# RTI-Dome-eth-ESP32.net
KiCad netlist of a schematic drawn in EAGLE
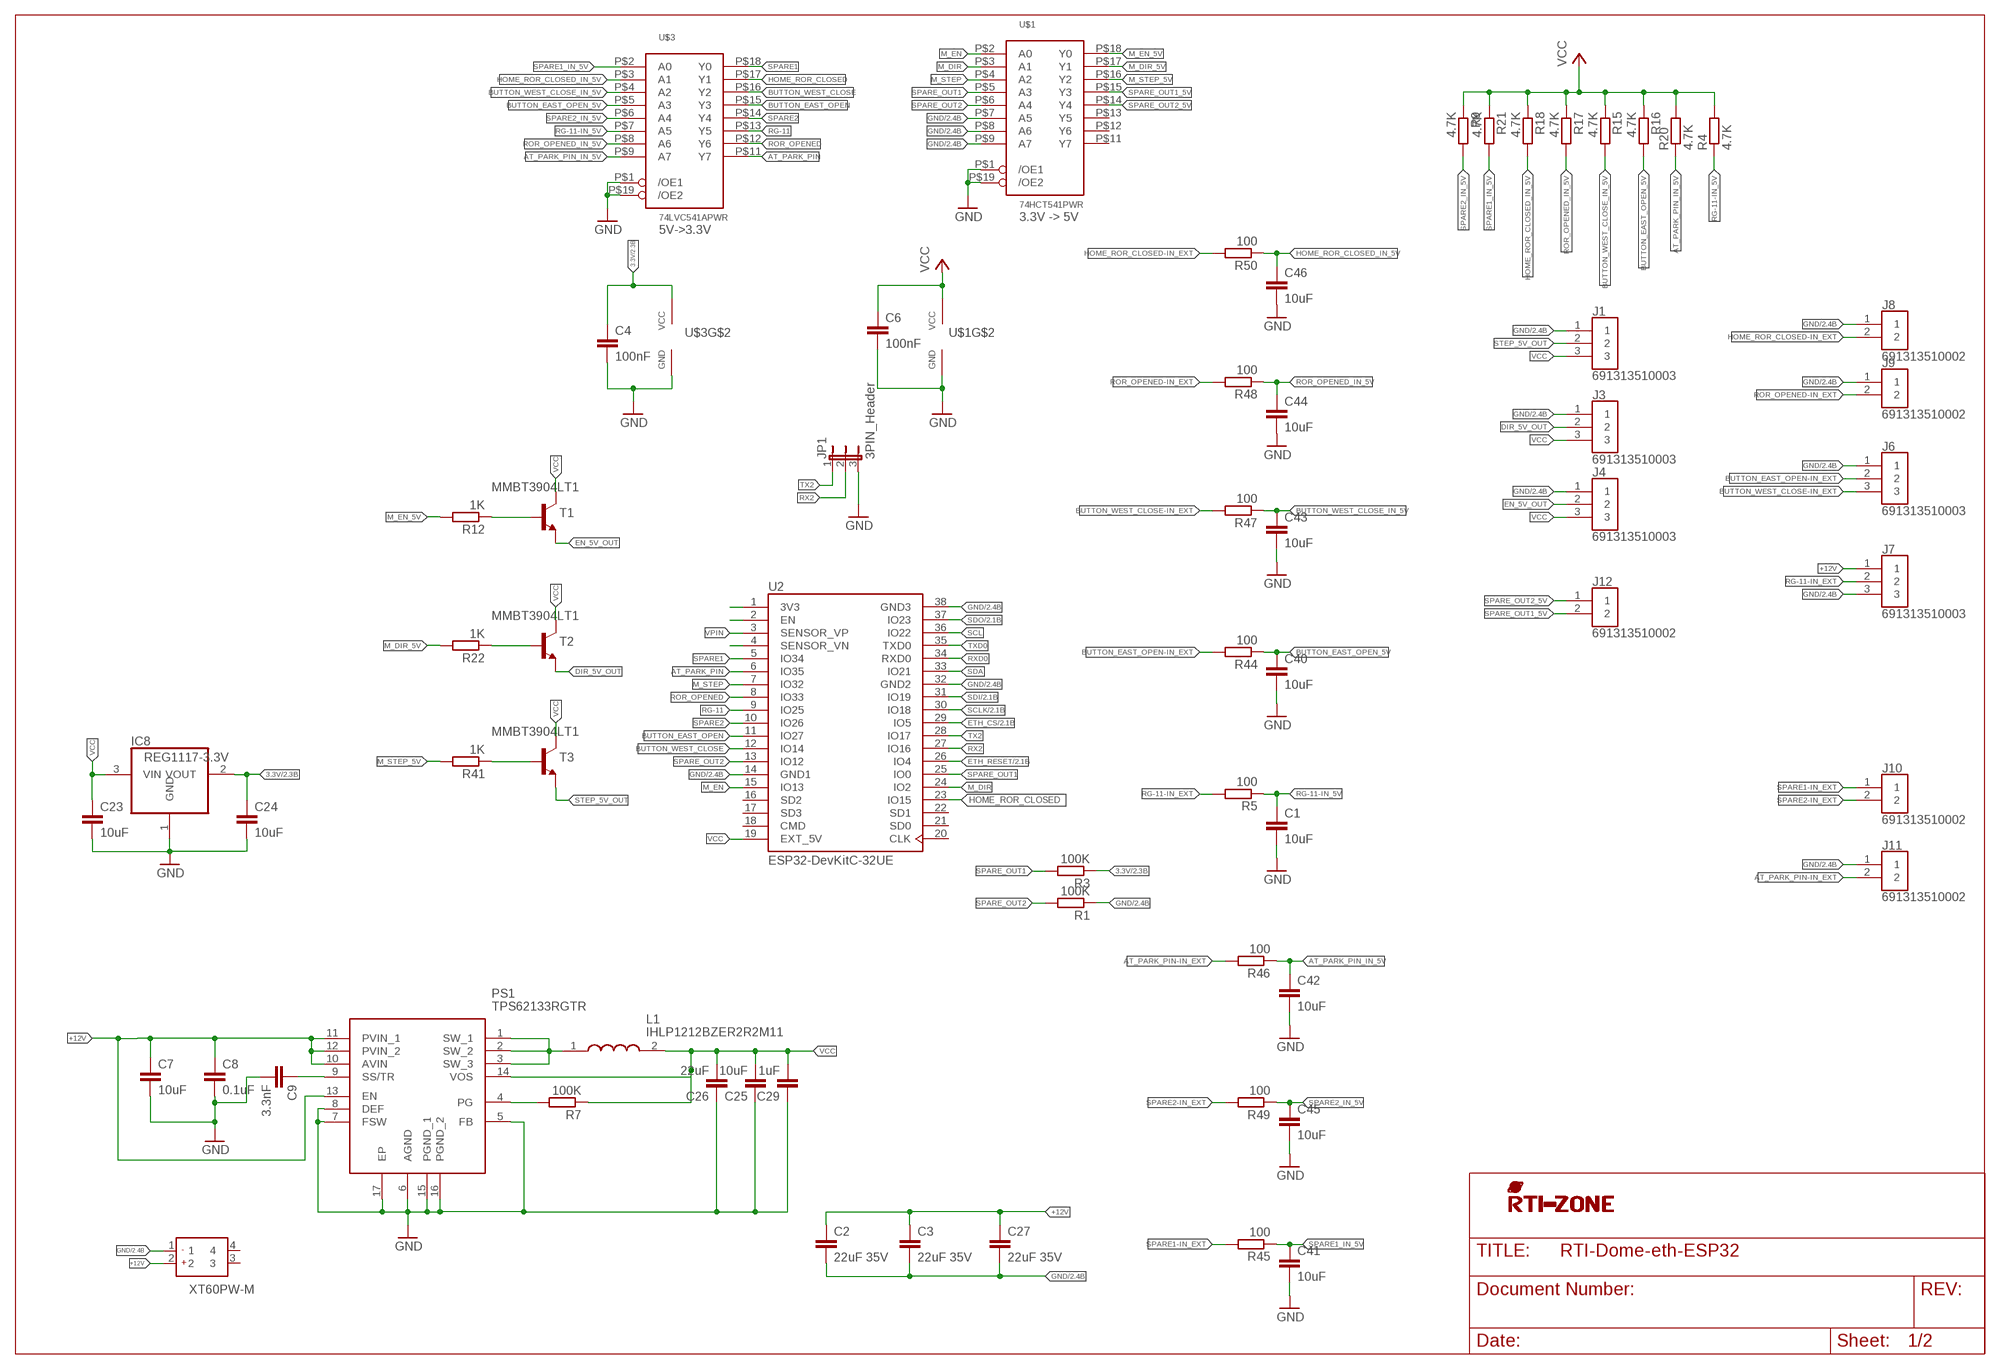
[diagram p0: schematic, sheet 1]
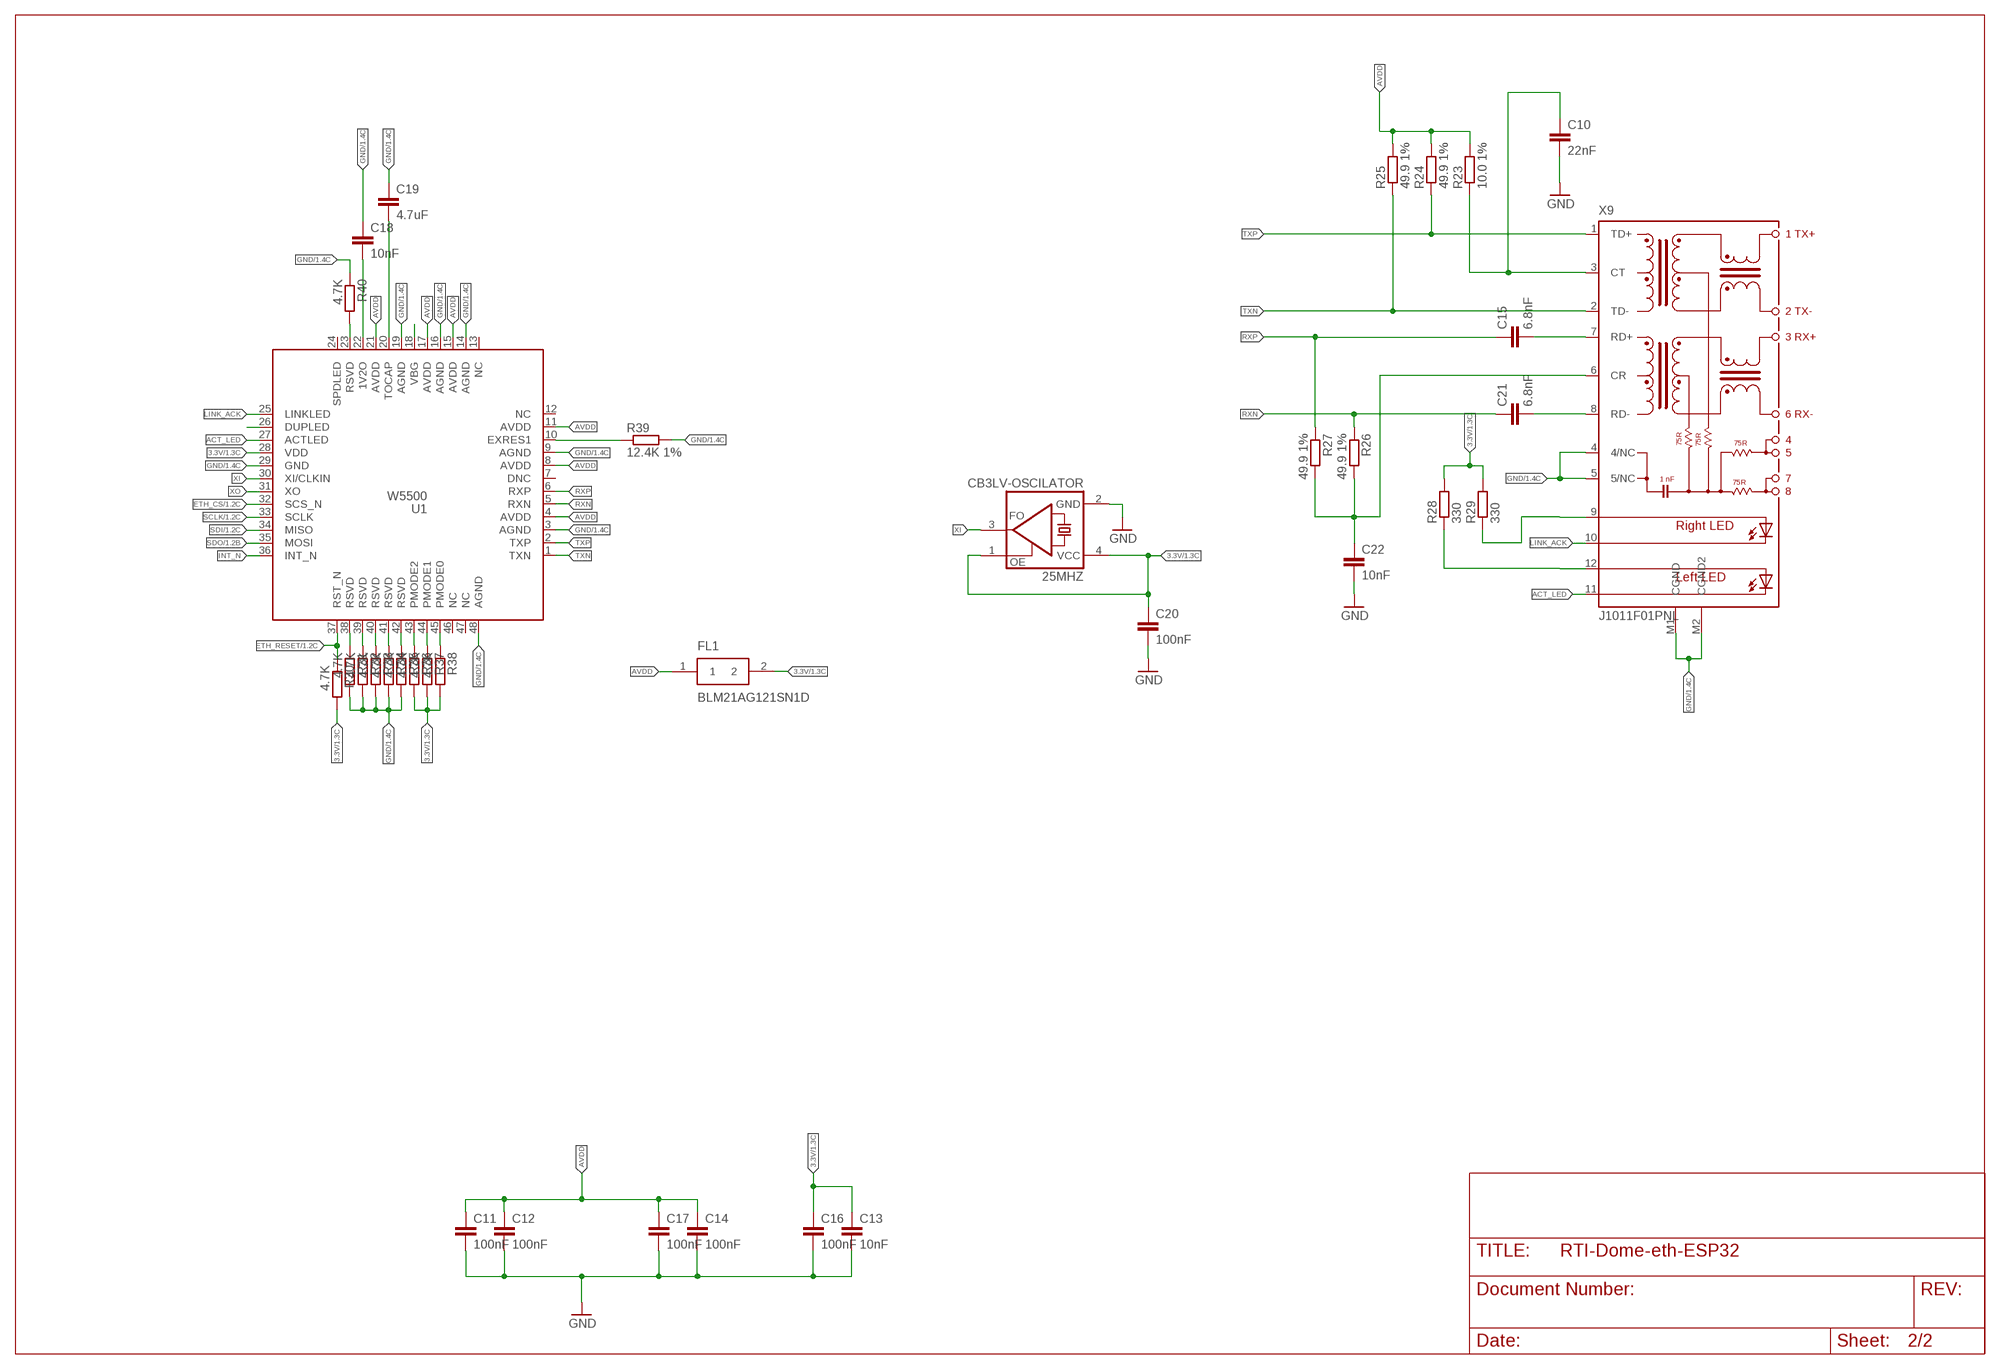
[diagram p1: schematic, sheet 2]

(export (version "E")
  (design (tool "Eeschema 10.0.6"))
  (components
    (comp (ref "C1")
      (value "10uF")
      (footprint "eagle-import:C0603")
      (fields (field (name "MPN") "CC0805KKX5R8BB106"))
      (libsource (lib "eagle-import") (part "C-EUC0603"))
    )
    (comp (ref "C2")
      (value "22uF 35V")
      (footprint "eagle-import:C1206")
      (libsource (lib "eagle-import") (part "C-EUC1206"))
    )
    (comp (ref "C3")
      (value "22uF 35V")
      (footprint "eagle-import:C1206")
      (libsource (lib "eagle-import") (part "C-EUC1206"))
    )
    (comp (ref "C4")
      (value "100nF")
      (footprint "eagle-import:C0603")
      (fields (field (name "MPN") "0805YD104KAT2A"))
      (libsource (lib "eagle-import") (part "C-EUC0603"))
    )
    (comp (ref "C6")
      (value "100nF")
      (footprint "eagle-import:C0603")
      (fields (field (name "MPN") "0805YD104KAT2A"))
      (libsource (lib "eagle-import") (part "C-EUC0603"))
    )
    (comp (ref "C7")
      (value "10uF")
      (footprint "eagle-import:C1206")
      (libsource (lib "eagle-import") (part "C-EUC1206"))
    )
    (comp (ref "C8")
      (value "0.1uF")
      (footprint "eagle-import:C1206")
      (libsource (lib "eagle-import") (part "C-EUC1206"))
    )
    (comp (ref "C9")
      (value "3.3nF")
      (footprint "eagle-import:C0805")
      (libsource (lib "eagle-import") (part "C-EUC0805"))
    )
    (comp (ref "C23")
      (value "10uF")
      (footprint "eagle-import:C0603")
      (fields (field (name "MPN") "CC0805KKX5R8BB106"))
      (libsource (lib "eagle-import") (part "C-EUC0603"))
    )
    (comp (ref "C24")
      (value "10uF")
      (footprint "eagle-import:C0603")
      (fields (field (name "MPN") "CC0805KKX5R8BB106"))
      (libsource (lib "eagle-import") (part "C-EUC0603"))
    )
    (comp (ref "C25")
      (value "10uF")
      (footprint "eagle-import:C0805")
      (libsource (lib "eagle-import") (part "C-EUC0805"))
    )
    (comp (ref "C26")
      (value "22uF")
      (footprint "eagle-import:C0805")
      (libsource (lib "eagle-import") (part "C-EUC0805"))
    )
    (comp (ref "C27")
      (value "22uF 35V")
      (footprint "eagle-import:C1206")
      (libsource (lib "eagle-import") (part "C-EUC1206"))
    )
    (comp (ref "C29")
      (value "1uF")
      (footprint "eagle-import:C0805")
      (libsource (lib "eagle-import") (part "C-EUC0805"))
    )
    (comp (ref "C40")
      (value "10uF")
      (footprint "eagle-import:C0603")
      (fields (field (name "MPN") "CC0805KKX5R8BB106"))
      (libsource (lib "eagle-import") (part "C-EUC0603"))
    )
    (comp (ref "C41")
      (value "10uF")
      (footprint "eagle-import:C0603")
      (fields (field (name "MPN") "CC0805KKX5R8BB106"))
      (libsource (lib "eagle-import") (part "C-EUC0603"))
    )
    (comp (ref "C42")
      (value "10uF")
      (footprint "eagle-import:C0603")
      (fields (field (name "MPN") "CC0805KKX5R8BB106"))
      (libsource (lib "eagle-import") (part "C-EUC0603"))
    )
    (comp (ref "C43")
      (value "10uF")
      (footprint "eagle-import:C0603")
      (fields (field (name "MPN") "CC0805KKX5R8BB106"))
      (libsource (lib "eagle-import") (part "C-EUC0603"))
    )
    (comp (ref "C44")
      (value "10uF")
      (footprint "eagle-import:C0603")
      (fields (field (name "MPN") "CC0805KKX5R8BB106"))
      (libsource (lib "eagle-import") (part "C-EUC0603"))
    )
    (comp (ref "C45")
      (value "10uF")
      (footprint "eagle-import:C0603")
      (fields (field (name "MPN") "CC0805KKX5R8BB106"))
      (libsource (lib "eagle-import") (part "C-EUC0603"))
    )
    (comp (ref "C46")
      (value "10uF")
      (footprint "eagle-import:C0603")
      (fields (field (name "MPN") "CC0805KKX5R8BB106"))
      (libsource (lib "eagle-import") (part "C-EUC0603"))
    )
    (comp (ref "IC8")
      (value "REG1117-3.3V")
      (footprint "eagle-import:SOT223")
      (fields (field (name "MPN") "REG1117") (field (name "MPN_1") "REG1117-3.3/2K5"))
      (libsource (lib "eagle-import") (part "REG1117"))
    )
    (comp (ref "J1")
      (value "691313510003")
      (footprint "eagle-import:691313510003")
      (fields (field (name "MOUSER_PART_NUMBER") "710-691313510003"))
      (libsource (lib "eagle-import") (part "691313510003"))
    )
    (comp (ref "J2")
      (value "XT60PW-M")
      (footprint "eagle-import:XT60PWM")
      (fields (field (name "LCSC_PART") "C98732"))
      (libsource (lib "eagle-import") (part "XT60PW-M"))
    )
    (comp (ref "J3")
      (value "691313510003")
      (footprint "eagle-import:691313510003")
      (fields (field (name "MOUSER_PART_NUMBER") "710-691313510003"))
      (libsource (lib "eagle-import") (part "691313510003"))
    )
    (comp (ref "J4")
      (value "691313510003")
      (footprint "eagle-import:691313510003")
      (fields (field (name "MOUSER_PART_NUMBER") "710-691313510003"))
      (libsource (lib "eagle-import") (part "691313510003"))
    )
    (comp (ref "J6")
      (value "691313510003")
      (footprint "eagle-import:691313510003")
      (fields (field (name "MOUSER_PART_NUMBER") "710-691313510003"))
      (libsource (lib "eagle-import") (part "691313510003"))
    )
    (comp (ref "J7")
      (value "691313510003")
      (footprint "eagle-import:691313510003")
      (fields (field (name "MOUSER_PART_NUMBER") "710-691313510003"))
      (libsource (lib "eagle-import") (part "691313510003"))
    )
    (comp (ref "J8")
      (value "691313510002")
      (footprint "eagle-import:SHDRRA2W100P0X508_1X2_1216X120")
      (fields (field (name "MOUSER_PART_NUMBER") "710-691313510002"))
      (libsource (lib "eagle-import") (part "691313510002"))
    )
    (comp (ref "J9")
      (value "691313510002")
      (footprint "eagle-import:SHDRRA2W100P0X508_1X2_1216X120")
      (fields (field (name "MOUSER_PART_NUMBER") "710-691313510002"))
      (libsource (lib "eagle-import") (part "691313510002"))
    )
    (comp (ref "J10")
      (value "691313510002")
      (footprint "eagle-import:SHDRRA2W100P0X508_1X2_1216X120")
      (fields (field (name "MOUSER_PART_NUMBER") "710-691313510002"))
      (libsource (lib "eagle-import") (part "691313510002"))
    )
    (comp (ref "J11")
      (value "691313510002")
      (footprint "eagle-import:SHDRRA2W100P0X508_1X2_1216X120")
      (fields (field (name "MOUSER_PART_NUMBER") "710-691313510002"))
      (libsource (lib "eagle-import") (part "691313510002"))
    )
    (comp (ref "J12")
      (value "691313510002")
      (footprint "eagle-import:SHDRRA2W100P0X508_1X2_1216X120")
      (fields (field (name "MOUSER_PART_NUMBER") "710-691313510002"))
      (libsource (lib "eagle-import") (part "691313510002"))
    )
    (comp (ref "JP1")
      (value "3PIN_Header")
      (footprint "eagle-import:JP2")
      (fields (field (name "LCSC_PART") "C19190477"))
      (libsource (lib "eagle-import") (part "JP2E"))
    )
    (comp (ref "L1")
      (value "IHLP1212BZER2R2M11")
      (footprint "eagle-import:INDPM3630X200N")
      (fields (field (name "LCSC_PART") "C553996") (field (name "MOUSER_PART_NUMBER") "70-IHLP1212BZER2R2M1"))
      (libsource (lib "eagle-import") (part "IHLP1212BZER2R2M11"))
    )
    (comp (ref "PS1")
      (value "TPS62133RGTR")
      (footprint "eagle-import:QFN50P300X300X100-17N")
      (fields (field (name "LCSC_PART") "C73973") (field (name "MOUSER_PART_NUMBER") "595-TPS62133RGTR"))
      (libsource (lib "eagle-import") (part "TPS62133RGTR"))
    )
    (comp (ref "R1")
      (value "100K")
      (footprint "eagle-import:R0603")
      (fields (field (name "MPN") "RT0805FRD07100RL"))
      (libsource (lib "eagle-import") (part "R-EU'0603'"))
    )
    (comp (ref "R3")
      (value "100K")
      (footprint "eagle-import:R0603")
      (fields (field (name "MPN") "RT0805FRD07100RL"))
      (libsource (lib "eagle-import") (part "R-EU'0603'"))
    )
    (comp (ref "R4")
      (value "4.7K")
      (footprint "eagle-import:R0603")
      (fields (field (name "MPN") "RT0805FRE074K7L"))
      (libsource (lib "eagle-import") (part "R-EU_R0603"))
    )
    (comp (ref "R5")
      (value "100")
      (footprint "eagle-import:R0603")
      (fields (field (name "MPN") "RT0805FRD07100RL"))
      (libsource (lib "eagle-import") (part "R-EU_R0603"))
    )
    (comp (ref "R7")
      (value "100K")
      (footprint "eagle-import:R0603")
      (libsource (lib "eagle-import") (part "R-EU_R0603"))
    )
    (comp (ref "R9")
      (value "4.7K")
      (footprint "eagle-import:R0603")
      (fields (field (name "MPN") "RT0805FRE074K7L"))
      (libsource (lib "eagle-import") (part "R-EU_R0603"))
    )
    (comp (ref "R12")
      (value "1K")
      (footprint "eagle-import:R0603")
      (fields (field (name "MPN") "RT0805FRE074K7L"))
      (libsource (lib "eagle-import") (part "R-EU_R0603"))
    )
    (comp (ref "R15")
      (value "4.7K")
      (footprint "eagle-import:R0603")
      (fields (field (name "MPN") "RT0805FRE074K7L"))
      (libsource (lib "eagle-import") (part "R-EU_R0603"))
    )
    (comp (ref "R16")
      (value "4.7K")
      (footprint "eagle-import:R0603")
      (fields (field (name "MPN") "RT0805FRE074K7L"))
      (libsource (lib "eagle-import") (part "R-EU_R0603"))
    )
    (comp (ref "R17")
      (value "4.7K")
      (footprint "eagle-import:R0603")
      (fields (field (name "MPN") "RT0805FRE074K7L"))
      (libsource (lib "eagle-import") (part "R-EU_R0603"))
    )
    (comp (ref "R18")
      (value "4.7K")
      (footprint "eagle-import:R0603")
      (fields (field (name "MPN") "RT0805FRE074K7L"))
      (libsource (lib "eagle-import") (part "R-EU_R0603"))
    )
    (comp (ref "R20")
      (value "4.7K")
      (footprint "eagle-import:R0603")
      (fields (field (name "MPN") "RT0805FRE074K7L"))
      (libsource (lib "eagle-import") (part "R-EU_R0603"))
    )
    (comp (ref "R21")
      (value "4.7K")
      (footprint "eagle-import:R0603")
      (fields (field (name "MPN") "RT0805FRE074K7L"))
      (libsource (lib "eagle-import") (part "R-EU_R0603"))
    )
    (comp (ref "R22")
      (value "1K")
      (footprint "eagle-import:R0603")
      (fields (field (name "MPN") "RT0805FRE074K7L"))
      (libsource (lib "eagle-import") (part "R-EU_R0603"))
    )
    (comp (ref "R41")
      (value "1K")
      (footprint "eagle-import:R0603")
      (fields (field (name "MPN") "RT0805FRE074K7L"))
      (libsource (lib "eagle-import") (part "R-EU_R0603"))
    )
    (comp (ref "R44")
      (value "100")
      (footprint "eagle-import:R0603")
      (fields (field (name "MPN") "RT0805FRD07100RL"))
      (libsource (lib "eagle-import") (part "R-EU_R0603"))
    )
    (comp (ref "R45")
      (value "100")
      (footprint "eagle-import:R0603")
      (fields (field (name "MPN") "RT0805FRD07100RL"))
      (libsource (lib "eagle-import") (part "R-EU_R0603"))
    )
    (comp (ref "R46")
      (value "100")
      (footprint "eagle-import:R0603")
      (fields (field (name "MPN") "RT0805FRD07100RL"))
      (libsource (lib "eagle-import") (part "R-EU_R0603"))
    )
    (comp (ref "R47")
      (value "100")
      (footprint "eagle-import:R0603")
      (fields (field (name "MPN") "RT0805FRD07100RL"))
      (libsource (lib "eagle-import") (part "R-EU_R0603"))
    )
    (comp (ref "R48")
      (value "100")
      (footprint "eagle-import:R0603")
      (fields (field (name "MPN") "RT0805FRD07100RL"))
      (libsource (lib "eagle-import") (part "R-EU_R0603"))
    )
    (comp (ref "R49")
      (value "100")
      (footprint "eagle-import:R0603")
      (fields (field (name "MPN") "RT0805FRD07100RL"))
      (libsource (lib "eagle-import") (part "R-EU_R0603"))
    )
    (comp (ref "R50")
      (value "100")
      (footprint "eagle-import:R0603")
      (fields (field (name "MPN") "RT0805FRD07100RL"))
      (libsource (lib "eagle-import") (part "R-EU_R0603"))
    )
    (comp (ref "T1")
      (value "MMBT3904LT1")
      (footprint "eagle-import:SOT23")
      (libsource (lib "eagle-import") (part "MMBT3904LT1"))
    )
    (comp (ref "T2")
      (value "MMBT3904LT1")
      (footprint "eagle-import:SOT23")
      (libsource (lib "eagle-import") (part "MMBT3904LT1"))
    )
    (comp (ref "T3")
      (value "MMBT3904LT1")
      (footprint "eagle-import:SOT23")
      (libsource (lib "eagle-import") (part "MMBT3904LT1"))
    )
    (comp (ref "U$1")
      (value "74HCT541PWR")
      (footprint "eagle-import:TSSOP20")
      (fields (field (name "LCSC_PART") "C131314"))
      (libsource (lib "eagle-import") (part "74541B"))
    )
    (comp (ref "U$3")
      (value "74LVC541APWR")
      (footprint "eagle-import:TSSOP20")
      (fields (field (name "LCSC_PART") "C6093"))
      (libsource (lib "eagle-import") (part "74541B"))
    )
    (comp (ref "U$4")
      (value "RTI-LOGO_BIG")
      (footprint "eagle-import:LOGO_BIG")
      (libsource (lib "eagle-import") (part "RTI-LOGO_BIG"))
    )
    (comp (ref "U2")
      (value "ESP32-DevKitC-32UE")
      (footprint "eagle-import:MODULE_ESP32-DEVKITC-32U")
      (libsource (lib "eagle-import") (part "ESP32-DEVKITC-32U"))
    )
    (comp (ref "25MHZ")
      (value "CB3LV-OSCILATOR")
      (footprint "eagle-import:SMD-7050_4P")
      (fields (field (name "MPN") "CB3LV-3I-25M0000"))
      (libsource (lib "eagle-import") (part "CB3LV-OSCILATOR"))
    )
    (comp (ref "C10")
      (value "22nF")
      (footprint "eagle-import:C0603")
      (fields (field (name "MPN") "CC0805JRX7R8BB223"))
      (libsource (lib "eagle-import") (part "C-EUC0603"))
    )
    (comp (ref "C11")
      (value "100nF")
      (footprint "eagle-import:C0603")
      (fields (field (name "MPN") "0805YD104KAT2A"))
      (libsource (lib "eagle-import") (part "C-EUC0603"))
    )
    (comp (ref "C12")
      (value "100nF")
      (footprint "eagle-import:C0603")
      (fields (field (name "MPN") "0805YD104KAT2A"))
      (libsource (lib "eagle-import") (part "C-EUC0603"))
    )
    (comp (ref "C13")
      (value "10nF")
      (footprint "eagle-import:C0603")
      (fields (field (name "MPN") " CC0805KRX7R9BB103"))
      (libsource (lib "eagle-import") (part "C-EUC0603"))
    )
    (comp (ref "C14")
      (value "100nF")
      (footprint "eagle-import:C0603")
      (fields (field (name "MPN") "0805YD104KAT2A"))
      (libsource (lib "eagle-import") (part "C-EUC0603"))
    )
    (comp (ref "C15")
      (value "6.8nF")
      (footprint "eagle-import:C0603")
      (fields (field (name "MPN") "C0805C682F4HACTU"))
      (libsource (lib "eagle-import") (part "C-EUC0603"))
    )
    (comp (ref "C16")
      (value "100nF")
      (footprint "eagle-import:C0603")
      (fields (field (name "MPN") "0805YD104KAT2A"))
      (libsource (lib "eagle-import") (part "C-EUC0603"))
    )
    (comp (ref "C17")
      (value "100nF")
      (footprint "eagle-import:C0603")
      (fields (field (name "MPN") "0805YD104KAT2A"))
      (libsource (lib "eagle-import") (part "C-EUC0603"))
    )
    (comp (ref "C18")
      (value "10nF")
      (footprint "eagle-import:C0603")
      (fields (field (name "MPN") " CC0805KRX7R9BB103"))
      (libsource (lib "eagle-import") (part "C-EUC0603"))
    )
    (comp (ref "C19")
      (value "4.7uF")
      (footprint "eagle-import:C0603")
      (fields (field (name "MPN") "C0805C475J3RACTU"))
      (libsource (lib "eagle-import") (part "C-EUC0603"))
    )
    (comp (ref "C20")
      (value "100nF")
      (footprint "eagle-import:C0603")
      (fields (field (name "MPN") "0805YD104KAT2A"))
      (libsource (lib "eagle-import") (part "C-EUC0603"))
    )
    (comp (ref "C21")
      (value "6.8nF")
      (footprint "eagle-import:C0603")
      (fields (field (name "MPN") "C0805C682F4HACTU"))
      (libsource (lib "eagle-import") (part "C-EUC0603"))
    )
    (comp (ref "C22")
      (value "10nF")
      (footprint "eagle-import:C0603")
      (fields (field (name "MPN") " CC0805KRX7R9BB103"))
      (libsource (lib "eagle-import") (part "C-EUC0603"))
    )
    (comp (ref "FL1")
      (value "BLM21AG121SN1D")
      (footprint "eagle-import:L0805")
      (libsource (lib "eagle-import") (part "BLM21AG121SN1D"))
    )
    (comp (ref "R23")
      (value "10.0 1%")
      (footprint "eagle-import:R0603")
      (fields (field (name "MPN") "C881123"))
      (libsource (lib "eagle-import") (part "R-EU_R0603"))
    )
    (comp (ref "R24")
      (value "49.9 1%")
      (footprint "eagle-import:R0603")
      (fields (field (name "MPN") "RC0805FR-0749R9L"))
      (libsource (lib "eagle-import") (part "R-EU_R0603"))
    )
    (comp (ref "R25")
      (value "49.9 1%")
      (footprint "eagle-import:R0603")
      (fields (field (name "MPN") "RC0805FR-0749R9L"))
      (libsource (lib "eagle-import") (part "R-EU_R0603"))
    )
    (comp (ref "R26")
      (value "49.9 1%")
      (footprint "eagle-import:R0603")
      (fields (field (name "MPN") "RC0805FR-0749R9L"))
      (libsource (lib "eagle-import") (part "R-EU_R0603"))
    )
    (comp (ref "R27")
      (value "49.9 1%")
      (footprint "eagle-import:R0603")
      (fields (field (name "MPN") "RC0805FR-0749R9L"))
      (libsource (lib "eagle-import") (part "R-EU_R0603"))
    )
    (comp (ref "R28")
      (value "330")
      (footprint "eagle-import:R0603")
      (fields (field (name "MPN") " RC0805JR-07330RL"))
      (libsource (lib "eagle-import") (part "R-EU_R0603"))
    )
    (comp (ref "R29")
      (value "330")
      (footprint "eagle-import:R0603")
      (fields (field (name "MPN") " RC0805JR-07330RL"))
      (libsource (lib "eagle-import") (part "R-EU_R0603"))
    )
    (comp (ref "R30")
      (value "4.7K")
      (footprint "eagle-import:R0603")
      (fields (field (name "MPN") "RT0805FRE074K7L"))
      (libsource (lib "eagle-import") (part "R-EU_R0603"))
    )
    (comp (ref "R31")
      (value "4.7K")
      (footprint "eagle-import:R0603")
      (fields (field (name "MPN") "RT0805FRE074K7L"))
      (libsource (lib "eagle-import") (part "R-EU_R0603"))
    )
    (comp (ref "R32")
      (value "4.7K")
      (footprint "eagle-import:R0603")
      (fields (field (name "MPN") "RT0805FRE074K7L"))
      (libsource (lib "eagle-import") (part "R-EU_R0603"))
    )
    (comp (ref "R33")
      (value "4.7K")
      (footprint "eagle-import:R0603")
      (fields (field (name "MPN") "RT0805FRE074K7L"))
      (libsource (lib "eagle-import") (part "R-EU_R0603"))
    )
    (comp (ref "R34")
      (value "4.7K")
      (footprint "eagle-import:R0603")
      (fields (field (name "MPN") "RT0805FRE074K7L"))
      (libsource (lib "eagle-import") (part "R-EU_R0603"))
    )
    (comp (ref "R35")
      (value "4.7K")
      (footprint "eagle-import:R0603")
      (fields (field (name "MPN") "RT0805FRE074K7L"))
      (libsource (lib "eagle-import") (part "R-EU_R0603"))
    )
    (comp (ref "R36")
      (value "4.7K")
      (footprint "eagle-import:R0603")
      (fields (field (name "MPN") "RT0805FRE074K7L"))
      (libsource (lib "eagle-import") (part "R-EU_R0603"))
    )
    (comp (ref "R37")
      (value "4.7K")
      (footprint "eagle-import:R0603")
      (fields (field (name "MPN") "RT0805FRE074K7L"))
      (libsource (lib "eagle-import") (part "R-EU_R0603"))
    )
    (comp (ref "R38")
      (value "4.7K")
      (footprint "eagle-import:R0603")
      (fields (field (name "MPN") "RT0805FRE074K7L"))
      (libsource (lib "eagle-import") (part "R-EU_R0603"))
    )
    (comp (ref "R39")
      (value "12.4K 1%")
      (footprint "eagle-import:R0603")
      (fields (field (name "MPN") "RC0805FR-0712K4L"))
      (libsource (lib "eagle-import") (part "R-EU_R0603"))
    )
    (comp (ref "R40")
      (value "4.7K")
      (footprint "eagle-import:R0603")
      (fields (field (name "MPN") "RT0805FRE074K7L"))
      (libsource (lib "eagle-import") (part "R-EU_R0603"))
    )
    (comp (ref "U1")
      (value "W5500")
      (footprint "eagle-import:LQFP48")
      (libsource (lib "eagle-import") (part "W5500"))
    )
    (comp (ref "X9")
      (value "J1011F01PNL")
      (footprint "eagle-import:J1011F01PNL")
      (libsource (lib "eagle-import") (part "J1011F01PNL"))
    )
  )
  (nets
    (net (code "1") (name "+12V") (class "Default")
      (node (ref "C2") (pin "1") (pinfunction "1_1") (pintype "passive"))
      (node (ref "C27") (pin "1") (pinfunction "1_1") (pintype "passive"))
      (node (ref "C3") (pin "1") (pinfunction "1_1") (pintype "passive"))
      (node (ref "C7") (pin "1") (pinfunction "1_1") (pintype "passive"))
      (node (ref "C8") (pin "1") (pinfunction "1_1") (pintype "passive"))
      (node (ref "J2") (pin "2") (pinfunction "2_2") (pintype "bidirectional"))
      (node (ref "J7") (pin "1") (pinfunction "1_1") (pintype "bidirectional"))
      (node (ref "PS1") (pin "10") (pinfunction "AVIN_10") (pintype "bidirectional"))
      (node (ref "PS1") (pin "11") (pinfunction "PVIN_1_11") (pintype "bidirectional"))
      (node (ref "PS1") (pin "12") (pinfunction "PVIN_2_12") (pintype "bidirectional"))
      (node (ref "PS1") (pin "13") (pinfunction "EN_13") (pintype "bidirectional"))
    )
    (net (code "2") (name "3.3V") (class "Default")
      (node (ref "25MHZ") (pin "1") (pinfunction "OE_1") (pintype "input"))
      (node (ref "25MHZ") (pin "4") (pinfunction "VDD_4") (pintype "power_in"))
      (node (ref "C13") (pin "1") (pinfunction "1_1") (pintype "passive"))
      (node (ref "C16") (pin "1") (pinfunction "1_1") (pintype "passive"))
      (node (ref "C20") (pin "1") (pinfunction "1_1") (pintype "passive"))
      (node (ref "C24") (pin "1") (pinfunction "1_1") (pintype "passive"))
      (node (ref "C4") (pin "1") (pinfunction "1_1") (pintype "passive"))
      (node (ref "FL1") (pin "2") (pinfunction "2_2") (pintype "bidirectional"))
      (node (ref "IC8") (pin "2") (pinfunction "VOUT_2") (pintype "output"))
      (node (ref "R28") (pin "2") (pinfunction "2_2") (pintype "passive"))
      (node (ref "R29") (pin "2") (pinfunction "2_2") (pintype "passive"))
      (node (ref "R3") (pin "1") (pinfunction "1_1") (pintype "passive"))
      (node (ref "R30") (pin "2") (pinfunction "2_2") (pintype "passive"))
      (node (ref "R36") (pin "2") (pinfunction "2_2") (pintype "passive"))
      (node (ref "R37") (pin "2") (pinfunction "2_2") (pintype "passive"))
      (node (ref "R38") (pin "2") (pinfunction "2_2") (pintype "passive"))
      (node (ref "U$3") (pin "P$20") (pinfunction "VCC_P$20") (pintype "power_in"))
      (node (ref "U1") (pin "28") (pinfunction "VDD_28") (pintype "passive"))
    )
    (net (code "3") (name "ACT_LED") (class "Default")
      (node (ref "U1") (pin "27") (pinfunction "ACTLED_27") (pintype "passive"))
      (node (ref "X9") (pin "11") (pinfunction "C-L_11") (pintype "passive"))
    )
    (net (code "4") (name "AT_PARK_PIN") (class "Default")
      (node (ref "U$3") (pin "P$11") (pinfunction "Y7_P$11") (pintype "output"))
      (node (ref "U2") (pin "6") (pinfunction "IO35_6") (pintype "bidirectional"))
    )
    (net (code "5") (name "AT_PARK_PIN-IN_EXT") (class "Default")
      (node (ref "J11") (pin "2") (pinfunction "2_2") (pintype "bidirectional"))
      (node (ref "R46") (pin "2") (pinfunction "2_2") (pintype "passive"))
    )
    (net (code "6") (name "AT_PARK_PIN_IN_5V") (class "Default")
      (node (ref "C42") (pin "1") (pinfunction "1_1") (pintype "passive"))
      (node (ref "R20") (pin "1") (pinfunction "1_1") (pintype "passive"))
      (node (ref "R46") (pin "1") (pinfunction "1_1") (pintype "passive"))
      (node (ref "U$3") (pin "P$9") (pinfunction "A7_P$9") (pintype "input"))
    )
    (net (code "7") (name "AVDD") (class "Default")
      (node (ref "C11") (pin "1") (pinfunction "1_1") (pintype "passive"))
      (node (ref "C12") (pin "1") (pinfunction "1_1") (pintype "passive"))
      (node (ref "C14") (pin "1") (pinfunction "1_1") (pintype "passive"))
      (node (ref "C17") (pin "1") (pinfunction "1_1") (pintype "passive"))
      (node (ref "FL1") (pin "1") (pinfunction "1_1") (pintype "bidirectional"))
      (node (ref "R23") (pin "2") (pinfunction "2_2") (pintype "passive"))
      (node (ref "R24") (pin "2") (pinfunction "2_2") (pintype "passive"))
      (node (ref "R25") (pin "2") (pinfunction "2_2") (pintype "passive"))
      (node (ref "U1") (pin "11") (pinfunction "AVDD_11") (pintype "passive"))
      (node (ref "U1") (pin "15") (pinfunction "AVDD_15") (pintype "passive"))
      (node (ref "U1") (pin "17") (pinfunction "AVDD_17") (pintype "passive"))
      (node (ref "U1") (pin "21") (pinfunction "AVDD_21") (pintype "passive"))
      (node (ref "U1") (pin "4") (pinfunction "AVDD_4") (pintype "passive"))
      (node (ref "U1") (pin "8") (pinfunction "AVDD_8") (pintype "passive"))
    )
    (net (code "8") (name "BUTTON_EAST_OPEN") (class "Default")
      (node (ref "U$3") (pin "P$15") (pinfunction "Y3_P$15") (pintype "output"))
      (node (ref "U2") (pin "11") (pinfunction "IO27_11") (pintype "bidirectional"))
    )
    (net (code "9") (name "BUTTON_EAST_OPEN-IN_EXT") (class "Default")
      (node (ref "J6") (pin "2") (pinfunction "2_2") (pintype "bidirectional"))
      (node (ref "R44") (pin "2") (pinfunction "2_2") (pintype "passive"))
    )
    (net (code "10") (name "BUTTON_EAST_OPEN_5V") (class "Default")
      (node (ref "C40") (pin "1") (pinfunction "1_1") (pintype "passive"))
      (node (ref "R16") (pin "2") (pinfunction "2_2") (pintype "passive"))
      (node (ref "R44") (pin "1") (pinfunction "1_1") (pintype "passive"))
      (node (ref "U$3") (pin "P$5") (pinfunction "A3_P$5") (pintype "input"))
    )
    (net (code "11") (name "BUTTON_WEST_CLOSE") (class "Default")
      (node (ref "U$3") (pin "P$16") (pinfunction "Y2_P$16") (pintype "output"))
      (node (ref "U2") (pin "12") (pinfunction "IO14_12") (pintype "bidirectional"))
    )
    (net (code "12") (name "BUTTON_WEST_CLOSE-IN_EXT") (class "Default")
      (node (ref "J6") (pin "3") (pinfunction "3_3") (pintype "bidirectional"))
      (node (ref "R47") (pin "2") (pinfunction "2_2") (pintype "passive"))
    )
    (net (code "13") (name "BUTTON_WEST_CLOSE_IN_5V") (class "Default")
      (node (ref "C43") (pin "1") (pinfunction "1_1") (pintype "passive"))
      (node (ref "R15") (pin "2") (pinfunction "2_2") (pintype "passive"))
      (node (ref "R47") (pin "1") (pinfunction "1_1") (pintype "passive"))
      (node (ref "U$3") (pin "P$4") (pinfunction "A2_P$4") (pintype "input"))
    )
    (net (code "14") (name "DIR_5V_OUT") (class "Default")
      (node (ref "J3") (pin "2") (pinfunction "2_2") (pintype "bidirectional"))
      (node (ref "T2") (pin "2") (pinfunction "E_2") (pintype "passive"))
    )
    (net (code "15") (name "EN_5V_OUT") (class "Default")
      (node (ref "J4") (pin "2") (pinfunction "2_2") (pintype "bidirectional"))
      (node (ref "T1") (pin "2") (pinfunction "E_2") (pintype "passive"))
    )
    (net (code "16") (name "ETH_CS") (class "Default")
      (node (ref "U1") (pin "32") (pinfunction "SCS_N_32") (pintype "passive"))
      (node (ref "U2") (pin "29") (pinfunction "IO5_29") (pintype "bidirectional"))
    )
    (net (code "17") (name "ETH_RESET") (class "Default")
      (node (ref "R30") (pin "1") (pinfunction "1_1") (pintype "passive"))
      (node (ref "U1") (pin "37") (pinfunction "RST_N_37") (pintype "passive"))
      (node (ref "U2") (pin "26") (pinfunction "IO4_26") (pintype "bidirectional"))
    )
    (net (code "18") (name "GND") (class "Default")
      (node (ref "25MHZ") (pin "2") (pinfunction "GND_2") (pintype "power_in"))
      (node (ref "C1") (pin "2") (pinfunction "2_2") (pintype "passive"))
      (node (ref "C10") (pin "2") (pinfunction "2_2") (pintype "passive"))
      (node (ref "C11") (pin "2") (pinfunction "2_2") (pintype "passive"))
      (node (ref "C12") (pin "2") (pinfunction "2_2") (pintype "passive"))
      (node (ref "C13") (pin "2") (pinfunction "2_2") (pintype "passive"))
      (node (ref "C14") (pin "2") (pinfunction "2_2") (pintype "passive"))
      (node (ref "C16") (pin "2") (pinfunction "2_2") (pintype "passive"))
      (node (ref "C17") (pin "2") (pinfunction "2_2") (pintype "passive"))
      (node (ref "C18") (pin "1") (pinfunction "1_1") (pintype "passive"))
      (node (ref "C19") (pin "1") (pinfunction "1_1") (pintype "passive"))
      (node (ref "C2") (pin "2") (pinfunction "2_2") (pintype "passive"))
      (node (ref "C20") (pin "2") (pinfunction "2_2") (pintype "passive"))
      (node (ref "C22") (pin "2") (pinfunction "2_2") (pintype "passive"))
      (node (ref "C23") (pin "2") (pinfunction "2_2") (pintype "passive"))
      (node (ref "C24") (pin "2") (pinfunction "2_2") (pintype "passive"))
      (node (ref "C25") (pin "1") (pinfunction "1_1") (pintype "passive"))
      (node (ref "C26") (pin "1") (pinfunction "1_1") (pintype "passive"))
      (node (ref "C27") (pin "2") (pinfunction "2_2") (pintype "passive"))
      (node (ref "C29") (pin "1") (pinfunction "1_1") (pintype "passive"))
      (node (ref "C3") (pin "2") (pinfunction "2_2") (pintype "passive"))
      (node (ref "C4") (pin "2") (pinfunction "2_2") (pintype "passive"))
      (node (ref "C40") (pin "2") (pinfunction "2_2") (pintype "passive"))
      (node (ref "C41") (pin "2") (pinfunction "2_2") (pintype "passive"))
      (node (ref "C42") (pin "2") (pinfunction "2_2") (pintype "passive"))
      (node (ref "C43") (pin "2") (pinfunction "2_2") (pintype "passive"))
      (node (ref "C44") (pin "2") (pinfunction "2_2") (pintype "passive"))
      (node (ref "C45") (pin "2") (pinfunction "2_2") (pintype "passive"))
      (node (ref "C46") (pin "2") (pinfunction "2_2") (pintype "passive"))
      (node (ref "C6") (pin "2") (pinfunction "2_2") (pintype "passive"))
      (node (ref "C7") (pin "2") (pinfunction "2_2") (pintype "passive"))
      (node (ref "C8") (pin "2") (pinfunction "2_2") (pintype "passive"))
      (node (ref "C9") (pin "2") (pinfunction "2_2") (pintype "passive"))
      (node (ref "IC8") (pin "1") (pinfunction "GND_1") (pintype "power_in"))
      (node (ref "J1") (pin "1") (pinfunction "1_1") (pintype "bidirectional"))
      (node (ref "J11") (pin "1") (pinfunction "1_1") (pintype "bidirectional"))
      (node (ref "J2") (pin "1") (pinfunction "1_1") (pintype "bidirectional"))
      (node (ref "J3") (pin "1") (pinfunction "1_1") (pintype "bidirectional"))
      (node (ref "J4") (pin "1") (pinfunction "1_1") (pintype "bidirectional"))
      (node (ref "J6") (pin "1") (pinfunction "1_1") (pintype "bidirectional"))
      (node (ref "J7") (pin "3") (pinfunction "3_3") (pintype "bidirectional"))
      (node (ref "J8") (pin "1") (pinfunction "1_1") (pintype "bidirectional"))
      (node (ref "J9") (pin "1") (pinfunction "1_1") (pintype "bidirectional"))
      (node (ref "JP1") (pin "3") (pinfunction "3_3") (pintype "passive"))
      (node (ref "PS1") (pin "15") (pinfunction "PGND_1_15") (pintype "bidirectional"))
      (node (ref "PS1") (pin "16") (pinfunction "PGND_2_16") (pintype "bidirectional"))
      (node (ref "PS1") (pin "17") (pinfunction "EP_17") (pintype "bidirectional"))
      (node (ref "PS1") (pin "5") (pinfunction "FB_5") (pintype "bidirectional"))
      (node (ref "PS1") (pin "6") (pinfunction "AGND_6") (pintype "bidirectional"))
      (node (ref "PS1") (pin "7") (pinfunction "FSW_7") (pintype "bidirectional"))
      (node (ref "PS1") (pin "8") (pinfunction "DEF_8") (pintype "bidirectional"))
      (node (ref "R1") (pin "1") (pinfunction "1_1") (pintype "passive"))
      (node (ref "R31") (pin "2") (pinfunction "2_2") (pintype "passive"))
      (node (ref "R32") (pin "2") (pinfunction "2_2") (pintype "passive"))
      (node (ref "R33") (pin "2") (pinfunction "2_2") (pintype "passive"))
      (node (ref "R34") (pin "2") (pinfunction "2_2") (pintype "passive"))
      (node (ref "R35") (pin "2") (pinfunction "2_2") (pintype "passive"))
      (node (ref "R39") (pin "2") (pinfunction "2_2") (pintype "passive"))
      (node (ref "R40") (pin "1") (pinfunction "1_1") (pintype "passive"))
      (node (ref "U$1") (pin "P$1") (pinfunction "/OE1_P$1") (pintype "input"))
      (node (ref "U$1") (pin "P$10") (pinfunction "GND_P$10") (pintype "power_in"))
      (node (ref "U$1") (pin "P$19") (pinfunction "/OE2_P$19") (pintype "input"))
      (node (ref "U$1") (pin "P$7") (pinfunction "A5_P$7") (pintype "input"))
      (node (ref "U$1") (pin "P$8") (pinfunction "A6_P$8") (pintype "input"))
      (node (ref "U$1") (pin "P$9") (pinfunction "A7_P$9") (pintype "input"))
      (node (ref "U$3") (pin "P$1") (pinfunction "/OE1_P$1") (pintype "input"))
      (node (ref "U$3") (pin "P$10") (pinfunction "GND_P$10") (pintype "power_in"))
      (node (ref "U$3") (pin "P$19") (pinfunction "/OE2_P$19") (pintype "input"))
      (node (ref "U1") (pin "14") (pinfunction "AGND_14") (pintype "passive"))
      (node (ref "U1") (pin "16") (pinfunction "AGND_16") (pintype "passive"))
      (node (ref "U1") (pin "19") (pinfunction "AGND_19") (pintype "passive"))
      (node (ref "U1") (pin "29") (pinfunction "GND_29") (pintype "passive"))
      (node (ref "U1") (pin "3") (pinfunction "AGND_3") (pintype "passive"))
      (node (ref "U1") (pin "48") (pinfunction "AGND_48") (pintype "passive"))
      (node (ref "U1") (pin "9") (pinfunction "AGND_9") (pintype "passive"))
      (node (ref "U2") (pin "14") (pinfunction "GND1_14") (pintype "power_in"))
      (node (ref "U2") (pin "32") (pinfunction "GND2_32") (pintype "power_in"))
      (node (ref "U2") (pin "38") (pinfunction "GND3_38") (pintype "power_in"))
      (node (ref "X9") (pin "4") (pinfunction "4/NC_4") (pintype "input"))
      (node (ref "X9") (pin "5") (pinfunction "5/NC_5") (pintype "input"))
      (node (ref "X9") (pin "M1") (pinfunction "CGND_M1") (pintype "bidirectional"))
      (node (ref "X9") (pin "M2") (pinfunction "CGND2_M2") (pintype "bidirectional"))
    )
    (net (code "19") (name "HOME_ROR_CLOSED") (class "Default")
      (node (ref "U$3") (pin "P$17") (pinfunction "Y1_P$17") (pintype "output"))
      (node (ref "U2") (pin "23") (pinfunction "IO15_23") (pintype "bidirectional"))
    )
    (net (code "20") (name "HOME_ROR_CLOSED-IN_EXT") (class "Default")
      (node (ref "J8") (pin "2") (pinfunction "2_2") (pintype "bidirectional"))
      (node (ref "R50") (pin "2") (pinfunction "2_2") (pintype "passive"))
    )
    (net (code "21") (name "HOME_ROR_CLOSED_IN_5V") (class "Default")
      (node (ref "C46") (pin "1") (pinfunction "1_1") (pintype "passive"))
      (node (ref "R18") (pin "2") (pinfunction "2_2") (pintype "passive"))
      (node (ref "R50") (pin "1") (pinfunction "1_1") (pintype "passive"))
      (node (ref "U$3") (pin "P$3") (pinfunction "A1_P$3") (pintype "input"))
    )
    (net (code "22") (name "INT_N") (class "Default")
      (node (ref "U1") (pin "36") (pinfunction "INT_N_36") (pintype "passive"))
    )
    (net (code "23") (name "LINK_ACK") (class "Default")
      (node (ref "U1") (pin "25") (pinfunction "LINKLED_25") (pintype "passive"))
      (node (ref "X9") (pin "10") (pinfunction "C-R_10") (pintype "passive"))
    )
    (net (code "24") (name "M_DIR") (class "Default")
      (node (ref "U$1") (pin "P$3") (pinfunction "A1_P$3") (pintype "input"))
      (node (ref "U2") (pin "24") (pinfunction "IO2_24") (pintype "bidirectional"))
    )
    (net (code "25") (name "M_DIR_5V") (class "Default")
      (node (ref "R22") (pin "2") (pinfunction "2_2") (pintype "passive"))
      (node (ref "U$1") (pin "P$17") (pinfunction "Y1_P$17") (pintype "output"))
    )
    (net (code "26") (name "M_EN") (class "Default")
      (node (ref "U$1") (pin "P$2") (pinfunction "A0_P$2") (pintype "input"))
      (node (ref "U2") (pin "15") (pinfunction "IO13_15") (pintype "bidirectional"))
    )
    (net (code "27") (name "M_EN_5V") (class "Default")
      (node (ref "R12") (pin "2") (pinfunction "2_2") (pintype "passive"))
      (node (ref "U$1") (pin "P$18") (pinfunction "Y0_P$18") (pintype "output"))
    )
    (net (code "28") (name "M_STEP") (class "Default")
      (node (ref "U$1") (pin "P$4") (pinfunction "A2_P$4") (pintype "input"))
      (node (ref "U2") (pin "7") (pinfunction "IO32_7") (pintype "bidirectional"))
    )
    (net (code "29") (name "M_STEP_5V") (class "Default")
      (node (ref "R41") (pin "2") (pinfunction "2_2") (pintype "passive"))
      (node (ref "U$1") (pin "P$16") (pinfunction "Y2_P$16") (pintype "output"))
    )
    (net (code "30") (name "Net-(PS1-PG)") (class "Default")
      (node (ref "PS1") (pin "4") (pinfunction "PG_4") (pintype "bidirectional"))
      (node (ref "R7") (pin "2") (pinfunction "2_2") (pintype "passive"))
    )
    (net (code "31") (name "Net-(PS1-SS{slash}TR)") (class "Default")
      (node (ref "C9") (pin "1") (pinfunction "1_1") (pintype "passive"))
      (node (ref "PS1") (pin "9") (pinfunction "SS/TR_9") (pintype "bidirectional"))
    )
    (net (code "32") (name "Net-(PS1-SW_1)") (class "Default")
      (node (ref "L1") (pin "1") (pinfunction "1_1") (pintype "bidirectional"))
      (node (ref "PS1") (pin "1") (pinfunction "SW_1_1") (pintype "bidirectional"))
      (node (ref "PS1") (pin "2") (pinfunction "SW_2_2") (pintype "bidirectional"))
      (node (ref "PS1") (pin "3") (pinfunction "SW_3_3") (pintype "bidirectional"))
    )
    (net (code "33") (name "Net-(R31-Pad1)") (class "Default")
      (node (ref "R31") (pin "1") (pinfunction "1_1") (pintype "passive"))
      (node (ref "U1") (pin "38") (pinfunction "RSVD_38") (pintype "passive"))
    )
    (net (code "34") (name "Net-(R32-Pad1)") (class "Default")
      (node (ref "R32") (pin "1") (pinfunction "1_1") (pintype "passive"))
      (node (ref "U1") (pin "39") (pinfunction "RSVD_39") (pintype "passive"))
    )
    (net (code "35") (name "Net-(R33-Pad1)") (class "Default")
      (node (ref "R33") (pin "1") (pinfunction "1_1") (pintype "passive"))
      (node (ref "U1") (pin "40") (pinfunction "RSVD_40") (pintype "passive"))
    )
    (net (code "36") (name "Net-(R34-Pad1)") (class "Default")
      (node (ref "R34") (pin "1") (pinfunction "1_1") (pintype "passive"))
      (node (ref "U1") (pin "41") (pinfunction "RSVD_41") (pintype "passive"))
    )
    (net (code "37") (name "Net-(R35-Pad1)") (class "Default")
      (node (ref "R35") (pin "1") (pinfunction "1_1") (pintype "passive"))
      (node (ref "U1") (pin "42") (pinfunction "RSVD_42") (pintype "passive"))
    )
    (net (code "38") (name "Net-(R40-Pad2)") (class "Default")
      (node (ref "R40") (pin "2") (pinfunction "2_2") (pintype "passive"))
      (node (ref "U1") (pin "23") (pinfunction "RSVD_23") (pintype "passive"))
    )
    (net (code "39") (name "Net-(T1-B)") (class "Default")
      (node (ref "R12") (pin "1") (pinfunction "1_1") (pintype "passive"))
      (node (ref "T1") (pin "1") (pinfunction "B_1") (pintype "passive"))
    )
    (net (code "40") (name "Net-(T2-B)") (class "Default")
      (node (ref "R22") (pin "1") (pinfunction "1_1") (pintype "passive"))
      (node (ref "T2") (pin "1") (pinfunction "B_1") (pintype "passive"))
    )
    (net (code "41") (name "Net-(T3-B)") (class "Default")
      (node (ref "R41") (pin "1") (pinfunction "1_1") (pintype "passive"))
      (node (ref "T3") (pin "1") (pinfunction "B_1") (pintype "passive"))
    )
    (net (code "42") (name "Net-(U1-1V2O)") (class "Default")
      (node (ref "C18") (pin "2") (pinfunction "2_2") (pintype "passive"))
      (node (ref "U1") (pin "22") (pinfunction "1V2O_22") (pintype "passive"))
    )
    (net (code "43") (name "Net-(U1-EXRES1)") (class "Default")
      (node (ref "R39") (pin "1") (pinfunction "1_1") (pintype "passive"))
      (node (ref "U1") (pin "10") (pinfunction "EXRES1_10") (pintype "passive"))
    )
    (net (code "44") (name "Net-(U1-PMODE0)") (class "Default")
      (node (ref "R38") (pin "1") (pinfunction "1_1") (pintype "passive"))
      (node (ref "U1") (pin "45") (pinfunction "PMODE0_45") (pintype "passive"))
    )
    (net (code "45") (name "Net-(U1-PMODE1)") (class "Default")
      (node (ref "R37") (pin "1") (pinfunction "1_1") (pintype "passive"))
      (node (ref "U1") (pin "44") (pinfunction "PMODE1_44") (pintype "passive"))
    )
    (net (code "46") (name "Net-(U1-PMODE2)") (class "Default")
      (node (ref "R36") (pin "1") (pinfunction "1_1") (pintype "passive"))
      (node (ref "U1") (pin "43") (pinfunction "PMODE2_43") (pintype "passive"))
    )
    (net (code "47") (name "Net-(U1-TOCAP)") (class "Default")
      (node (ref "C19") (pin "2") (pinfunction "2_2") (pintype "passive"))
      (node (ref "U1") (pin "20") (pinfunction "TOCAP_20") (pintype "passive"))
    )
    (net (code "48") (name "Net-(X9-A-R)") (class "Default")
      (node (ref "R29") (pin "1") (pinfunction "1_1") (pintype "passive"))
      (node (ref "X9") (pin "9") (pinfunction "A-R_9") (pintype "passive"))
    )
    (net (code "49") (name "Net-(X9-AL)") (class "Default")
      (node (ref "R28") (pin "1") (pinfunction "1_1") (pintype "passive"))
      (node (ref "X9") (pin "12") (pinfunction "AL_12") (pintype "passive"))
    )
    (net (code "50") (name "Net-(X9-CR)") (class "Default")
      (node (ref "C22") (pin "1") (pinfunction "1_1") (pintype "passive"))
      (node (ref "R26") (pin "2") (pinfunction "2_2") (pintype "passive"))
      (node (ref "R27") (pin "2") (pinfunction "2_2") (pintype "passive"))
      (node (ref "X9") (pin "6") (pinfunction "CR_6") (pintype "input"))
    )
    (net (code "51") (name "Net-(X9-CT)") (class "Default")
      (node (ref "C10") (pin "1") (pinfunction "1_1") (pintype "passive"))
      (node (ref "R23") (pin "1") (pinfunction "1_1") (pintype "passive"))
      (node (ref "X9") (pin "3") (pinfunction "CT_3") (pintype "input"))
    )
    (net (code "52") (name "Net-(X9-RD+)") (class "Default")
      (node (ref "C15") (pin "2") (pinfunction "2_2") (pintype "passive"))
      (node (ref "X9") (pin "7") (pinfunction "RD+_7") (pintype "input"))
    )
    (net (code "53") (name "Net-(X9-RD-)") (class "Default")
      (node (ref "C21") (pin "2") (pinfunction "2_2") (pintype "passive"))
      (node (ref "X9") (pin "8") (pinfunction "RD-_8") (pintype "input"))
    )
    (net (code "54") (name "RG-11") (class "Default")
      (node (ref "U$3") (pin "P$13") (pinfunction "Y5_P$13") (pintype "output"))
      (node (ref "U2") (pin "9") (pinfunction "IO25_9") (pintype "bidirectional"))
    )
    (net (code "55") (name "RG-11-IN_5V") (class "Default")
      (node (ref "C1") (pin "1") (pinfunction "1_1") (pintype "passive"))
      (node (ref "R4") (pin "1") (pinfunction "1_1") (pintype "passive"))
      (node (ref "R5") (pin "1") (pinfunction "1_1") (pintype "passive"))
      (node (ref "U$3") (pin "P$7") (pinfunction "A5_P$7") (pintype "input"))
    )
    (net (code "56") (name "RG-11-IN_EXT") (class "Default")
      (node (ref "J7") (pin "2") (pinfunction "2_2") (pintype "bidirectional"))
      (node (ref "R5") (pin "2") (pinfunction "2_2") (pintype "passive"))
    )
    (net (code "57") (name "ROR_OPENED") (class "Default")
      (node (ref "U$3") (pin "P$12") (pinfunction "Y6_P$12") (pintype "output"))
      (node (ref "U2") (pin "8") (pinfunction "IO33_8") (pintype "bidirectional"))
    )
    (net (code "58") (name "ROR_OPENED-IN_EXT") (class "Default")
      (node (ref "J9") (pin "2") (pinfunction "2_2") (pintype "bidirectional"))
      (node (ref "R48") (pin "2") (pinfunction "2_2") (pintype "passive"))
    )
    (net (code "59") (name "ROR_OPENED_IN_5V") (class "Default")
      (node (ref "C44") (pin "1") (pinfunction "1_1") (pintype "passive"))
      (node (ref "R17") (pin "2") (pinfunction "2_2") (pintype "passive"))
      (node (ref "R48") (pin "1") (pinfunction "1_1") (pintype "passive"))
      (node (ref "U$3") (pin "P$8") (pinfunction "A6_P$8") (pintype "input"))
    )
    (net (code "60") (name "RX2") (class "Default")
      (node (ref "JP1") (pin "2") (pinfunction "2_2") (pintype "passive"))
      (node (ref "U2") (pin "27") (pinfunction "IO16_27") (pintype "bidirectional"))
    )
    (net (code "61") (name "RXD0") (class "Default")
      (node (ref "U2") (pin "34") (pinfunction "RXD0_34") (pintype "input"))
    )
    (net (code "62") (name "RXN") (class "Default")
      (node (ref "C21") (pin "1") (pinfunction "1_1") (pintype "passive"))
      (node (ref "R26") (pin "1") (pinfunction "1_1") (pintype "passive"))
      (node (ref "U1") (pin "5") (pinfunction "RXN_5") (pintype "passive"))
    )
    (net (code "63") (name "RXP") (class "Default")
      (node (ref "C15") (pin "1") (pinfunction "1_1") (pintype "passive"))
      (node (ref "R27") (pin "1") (pinfunction "1_1") (pintype "passive"))
      (node (ref "U1") (pin "6") (pinfunction "RXP_6") (pintype "passive"))
    )
    (net (code "64") (name "SCL") (class "Default")
      (node (ref "U2") (pin "36") (pinfunction "IO22_36") (pintype "bidirectional"))
    )
    (net (code "65") (name "SCLK") (class "Default")
      (node (ref "U1") (pin "33") (pinfunction "SCLK_33") (pintype "passive"))
      (node (ref "U2") (pin "30") (pinfunction "IO18_30") (pintype "bidirectional"))
    )
    (net (code "66") (name "SDA") (class "Default")
      (node (ref "U2") (pin "33") (pinfunction "IO21_33") (pintype "bidirectional"))
    )
    (net (code "67") (name "SDI") (class "Default")
      (node (ref "U1") (pin "34") (pinfunction "MISO_34") (pintype "passive"))
      (node (ref "U2") (pin "31") (pinfunction "IO19_31") (pintype "bidirectional"))
    )
    (net (code "68") (name "SDO") (class "Default")
      (node (ref "U1") (pin "35") (pinfunction "MOSI_35") (pintype "passive"))
      (node (ref "U2") (pin "37") (pinfunction "IO23_37") (pintype "bidirectional"))
    )
    (net (code "69") (name "SPARE1") (class "Default")
      (node (ref "U$3") (pin "P$18") (pinfunction "Y0_P$18") (pintype "output"))
      (node (ref "U2") (pin "5") (pinfunction "IO34_5") (pintype "bidirectional"))
    )
    (net (code "70") (name "SPARE1-IN_EXT") (class "Default")
      (node (ref "J10") (pin "1") (pinfunction "1_1") (pintype "bidirectional"))
      (node (ref "R45") (pin "2") (pinfunction "2_2") (pintype "passive"))
    )
    (net (code "71") (name "SPARE1_IN_5V") (class "Default")
      (node (ref "C41") (pin "1") (pinfunction "1_1") (pintype "passive"))
      (node (ref "R21") (pin "2") (pinfunction "2_2") (pintype "passive"))
      (node (ref "R45") (pin "1") (pinfunction "1_1") (pintype "passive"))
      (node (ref "U$3") (pin "P$2") (pinfunction "A0_P$2") (pintype "input"))
    )
    (net (code "72") (name "SPARE2") (class "Default")
      (node (ref "U$3") (pin "P$14") (pinfunction "Y4_P$14") (pintype "output"))
      (node (ref "U2") (pin "10") (pinfunction "IO26_10") (pintype "bidirectional"))
    )
    (net (code "73") (name "SPARE2-IN_EXT") (class "Default")
      (node (ref "J10") (pin "2") (pinfunction "2_2") (pintype "bidirectional"))
      (node (ref "R49") (pin "2") (pinfunction "2_2") (pintype "passive"))
    )
    (net (code "74") (name "SPARE2_IN_5V") (class "Default")
      (node (ref "C45") (pin "1") (pinfunction "1_1") (pintype "passive"))
      (node (ref "R49") (pin "1") (pinfunction "1_1") (pintype "passive"))
      (node (ref "R9") (pin "2") (pinfunction "2_2") (pintype "passive"))
      (node (ref "U$3") (pin "P$6") (pinfunction "A4_P$6") (pintype "input"))
    )
    (net (code "75") (name "SPARE_OUT1") (class "Default")
      (node (ref "R3") (pin "2") (pinfunction "2_2") (pintype "passive"))
      (node (ref "U$1") (pin "P$5") (pinfunction "A3_P$5") (pintype "input"))
      (node (ref "U2") (pin "25") (pinfunction "IO0_25") (pintype "bidirectional"))
    )
    (net (code "76") (name "SPARE_OUT1_5V") (class "Default")
      (node (ref "J12") (pin "2") (pinfunction "2_2") (pintype "bidirectional"))
      (node (ref "U$1") (pin "P$15") (pinfunction "Y3_P$15") (pintype "output"))
    )
    (net (code "77") (name "SPARE_OUT2") (class "Default")
      (node (ref "R1") (pin "2") (pinfunction "2_2") (pintype "passive"))
      (node (ref "U$1") (pin "P$6") (pinfunction "A4_P$6") (pintype "input"))
      (node (ref "U2") (pin "13") (pinfunction "IO12_13") (pintype "bidirectional"))
    )
    (net (code "78") (name "SPARE_OUT2_5V") (class "Default")
      (node (ref "J12") (pin "1") (pinfunction "1_1") (pintype "bidirectional"))
      (node (ref "U$1") (pin "P$14") (pinfunction "Y4_P$14") (pintype "output"))
    )
    (net (code "79") (name "STEP_5V_OUT") (class "Default")
      (node (ref "J1") (pin "2") (pinfunction "2_2") (pintype "bidirectional"))
      (node (ref "T3") (pin "2") (pinfunction "E_2") (pintype "passive"))
    )
    (net (code "80") (name "TX2") (class "Default")
      (node (ref "JP1") (pin "1") (pinfunction "1_1") (pintype "passive"))
      (node (ref "U2") (pin "28") (pinfunction "IO17_28") (pintype "bidirectional"))
    )
    (net (code "81") (name "TXD0") (class "Default")
      (node (ref "U2") (pin "35") (pinfunction "TXD0_35") (pintype "output"))
    )
    (net (code "82") (name "TXN") (class "Default")
      (node (ref "R25") (pin "1") (pinfunction "1_1") (pintype "passive"))
      (node (ref "U1") (pin "1") (pinfunction "TXN_1") (pintype "passive"))
      (node (ref "X9") (pin "2") (pinfunction "TD-_2") (pintype "input"))
    )
    (net (code "83") (name "TXP") (class "Default")
      (node (ref "R24") (pin "1") (pinfunction "1_1") (pintype "passive"))
      (node (ref "U1") (pin "2") (pinfunction "TXP_2") (pintype "passive"))
      (node (ref "X9") (pin "1") (pinfunction "TD+_1") (pintype "input"))
    )
    (net (code "84") (name "VCC") (class "Default")
      (node (ref "C23") (pin "1") (pinfunction "1_1") (pintype "passive"))
      (node (ref "C25") (pin "2") (pinfunction "2_2") (pintype "passive"))
      (node (ref "C26") (pin "2") (pinfunction "2_2") (pintype "passive"))
      (node (ref "C29") (pin "2") (pinfunction "2_2") (pintype "passive"))
      (node (ref "C6") (pin "1") (pinfunction "1_1") (pintype "passive"))
      (node (ref "IC8") (pin "3") (pinfunction "VIN_3") (pintype "input"))
      (node (ref "J1") (pin "3") (pinfunction "3_3") (pintype "bidirectional"))
      (node (ref "J3") (pin "3") (pinfunction "3_3") (pintype "bidirectional"))
      (node (ref "J4") (pin "3") (pinfunction "3_3") (pintype "bidirectional"))
      (node (ref "L1") (pin "2") (pinfunction "2_2") (pintype "bidirectional"))
      (node (ref "PS1") (pin "14") (pinfunction "VOS_14") (pintype "bidirectional"))
      (node (ref "R15") (pin "1") (pinfunction "1_1") (pintype "passive"))
      (node (ref "R16") (pin "1") (pinfunction "1_1") (pintype "passive"))
      (node (ref "R17") (pin "1") (pinfunction "1_1") (pintype "passive"))
      (node (ref "R18") (pin "1") (pinfunction "1_1") (pintype "passive"))
      (node (ref "R20") (pin "2") (pinfunction "2_2") (pintype "passive"))
      (node (ref "R21") (pin "1") (pinfunction "1_1") (pintype "passive"))
      (node (ref "R4") (pin "2") (pinfunction "2_2") (pintype "passive"))
      (node (ref "R7") (pin "1") (pinfunction "1_1") (pintype "passive"))
      (node (ref "R9") (pin "1") (pinfunction "1_1") (pintype "passive"))
      (node (ref "T1") (pin "3") (pinfunction "C_3") (pintype "passive"))
      (node (ref "T2") (pin "3") (pinfunction "C_3") (pintype "passive"))
      (node (ref "T3") (pin "3") (pinfunction "C_3") (pintype "passive"))
      (node (ref "U$1") (pin "P$20") (pinfunction "VCC_P$20") (pintype "power_in"))
      (node (ref "U2") (pin "19") (pinfunction "EXT_5V_19") (pintype "power_in"))
    )
    (net (code "85") (name "VPIN") (class "Default")
      (node (ref "U2") (pin "3") (pinfunction "SENSOR_VP_3") (pintype "input"))
    )
    (net (code "86") (name "XI") (class "Default")
      (node (ref "25MHZ") (pin "3") (pinfunction "FO_3") (pintype "output"))
      (node (ref "U1") (pin "30") (pinfunction "XI/CLKIN_30") (pintype "passive"))
    )
    (net (code "87") (name "XO") (class "Default")
      (node (ref "U1") (pin "31") (pinfunction "XO_31") (pintype "passive"))
    )
    (net (code "88") (name "unconnected-(J2-Pad3)") (class "Default")
      (node (ref "J2") (pin "3") (pinfunction "3_3") (pintype "bidirectional"))
    )
    (net (code "89") (name "unconnected-(J2-Pad4)") (class "Default")
      (node (ref "J2") (pin "4") (pinfunction "4_4") (pintype "bidirectional"))
    )
    (net (code "90") (name "unconnected-(U$1A-Y5-PadP$13)") (class "Default")
      (node (ref "U$1") (pin "P$13") (pinfunction "Y5_P$13") (pintype "output"))
    )
    (net (code "91") (name "unconnected-(U$1A-Y6-PadP$12)") (class "Default")
      (node (ref "U$1") (pin "P$12") (pinfunction "Y6_P$12") (pintype "output"))
    )
    (net (code "92") (name "unconnected-(U$1A-Y7-PadP$11)") (class "Default")
      (node (ref "U$1") (pin "P$11") (pinfunction "Y7_P$11") (pintype "output"))
    )
    (net (code "93") (name "unconnected-(U1-DNC-Pad7)") (class "Default")
      (node (ref "U1") (pin "7") (pinfunction "DNC_7") (pintype "passive"))
    )
    (net (code "94") (name "unconnected-(U1-DUPLED-Pad26)") (class "Default")
      (node (ref "U1") (pin "26") (pinfunction "DUPLED_26") (pintype "passive"))
    )
    (net (code "95") (name "unconnected-(U1-NC-Pad12)") (class "Default")
      (node (ref "U1") (pin "12") (pinfunction "NC_12") (pintype "passive"))
    )
    (net (code "96") (name "unconnected-(U1-NC-Pad13)") (class "Default")
      (node (ref "U1") (pin "13") (pinfunction "NC_13") (pintype "passive"))
    )
    (net (code "97") (name "unconnected-(U1-NC-Pad46)") (class "Default")
      (node (ref "U1") (pin "46") (pinfunction "NC_46") (pintype "passive"))
    )
    (net (code "98") (name "unconnected-(U1-NC-Pad47)") (class "Default")
      (node (ref "U1") (pin "47") (pinfunction "NC_47") (pintype "passive"))
    )
    (net (code "99") (name "unconnected-(U1-SPDLED-Pad24)") (class "Default")
      (node (ref "U1") (pin "24") (pinfunction "SPDLED_24") (pintype "passive"))
    )
    (net (code "100") (name "unconnected-(U1-VBG-Pad18)") (class "Default")
      (node (ref "U1") (pin "18") (pinfunction "VBG_18") (pintype "passive"))
    )
    (net (code "101") (name "unconnected-(U2-3V3-Pad1)") (class "Default")
      (node (ref "U2") (pin "1") (pinfunction "3V3_1") (pintype "power_in"))
    )
    (net (code "102") (name "unconnected-(U2-CLK-Pad20)") (class "Default")
      (node (ref "U2") (pin "20") (pinfunction "CLK_20") (pintype "input"))
    )
    (net (code "103") (name "unconnected-(U2-CMD-Pad18)") (class "Default")
      (node (ref "U2") (pin "18") (pinfunction "CMD_18") (pintype "bidirectional"))
    )
    (net (code "104") (name "unconnected-(U2-EN-Pad2)") (class "Default")
      (node (ref "U2") (pin "2") (pinfunction "EN_2") (pintype "input"))
    )
    (net (code "105") (name "unconnected-(U2-SD0-Pad21)") (class "Default")
      (node (ref "U2") (pin "21") (pinfunction "SD0_21") (pintype "bidirectional"))
    )
    (net (code "106") (name "unconnected-(U2-SD1-Pad22)") (class "Default")
      (node (ref "U2") (pin "22") (pinfunction "SD1_22") (pintype "bidirectional"))
    )
    (net (code "107") (name "unconnected-(U2-SD2-Pad16)") (class "Default")
      (node (ref "U2") (pin "16") (pinfunction "SD2_16") (pintype "bidirectional"))
    )
    (net (code "108") (name "unconnected-(U2-SD3-Pad17)") (class "Default")
      (node (ref "U2") (pin "17") (pinfunction "SD3_17") (pintype "bidirectional"))
    )
    (net (code "109") (name "unconnected-(U2-SENSOR_VN-Pad4)") (class "Default")
      (node (ref "U2") (pin "4") (pinfunction "SENSOR_VN_4") (pintype "input"))
    )
  )
)
